# headtracking.net
KiCad netlist of a schematic drawn in Altium Designer
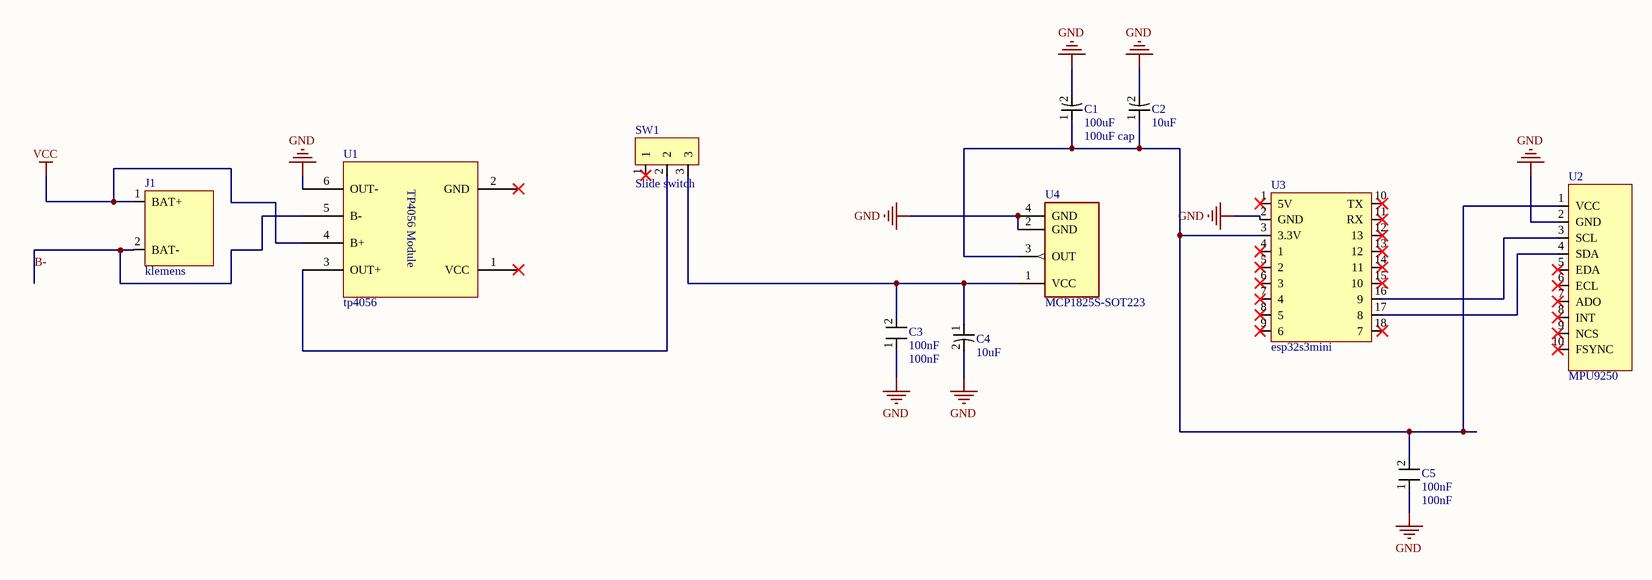
[diagram p0: headtracking.SchDoc]

(export (version "E")
  (design (tool "Eeschema 10.0.6"))
  (components
    (comp (ref "C1")
      (value "100uF cap")
      (footprint "electrytic cap")
      (fields (field (name "ALTIUM_VALUE") "100uF"))
      (libsource (lib "Integrated_Library1") (part "100uF cap"))
    )
    (comp (ref "C2")
      (value "10uF")
      (footprint "electrytic cap")
      (libsource (lib "Integrated_Library1") (part "10uF cap"))
    )
    (comp (ref "C3")
      (value "100nF")
      (footprint "ceramic cap")
      (fields (field (name "ALTIUM_VALUE") "100nF"))
      (libsource (lib "Integrated_Library1") (part "100nf cap"))
    )
    (comp (ref "C4")
      (value "10uF")
      (footprint "electrytic cap")
      (libsource (lib "Integrated_Library1") (part "10uF cap"))
    )
    (comp (ref "C5")
      (value "100nF")
      (footprint "ceramic cap")
      (fields (field (name "ALTIUM_VALUE") "100nF"))
      (libsource (lib "Integrated_Library1") (part "100nf cap"))
    )
    (comp (ref "J1")
      (value "klemens")
      (footprint "PCB_Klemens")
      (libsource (lib "Integrated_Library1") (part "klemens"))
    )
    (comp (ref "SW1")
      (value "Slide switch")
      (footprint "slide switch")
      (libsource (lib "Integrated_Library1") (part "Slide switch"))
    )
    (comp (ref "U1")
      (value "tp4056")
      (footprint "tp4056")
      (libsource (lib "Integrated_Library1") (part "tp4056"))
    )
    (comp (ref "U2")
      (value "MPU9250")
      (footprint "mpu9250")
      (libsource (lib "Integrated_Library1") (part "MPU9250"))
    )
    (comp (ref "U3")
      (value "esp32s3mini")
      (footprint "ESP32_S3_MINI")
      (libsource (lib "Integrated_Library1") (part "esp32s3mini"))
    )
    (comp (ref "U4")
      (value "MCP1825S-SOT223")
      (footprint "SOT-223 - regulator")
      (fields (field (name "MF") "Smartec") (field (name "MP") "SMT172-SOT223"))
      (libsource (lib "Integrated_Library1") (part "MCP1825S-SOT223"))
    )
  )
  (nets
    (net (code "1") (name "/B-") (class "Default")
      (node (ref "J1") (pin "2") (pinfunction "BAT-_2") (pintype "passive"))
      (node (ref "U1") (pin "5") (pinfunction "B-_5") (pintype "passive"))
    )
    (net (code "2") (name "GND") (class "Default")
      (node (ref "C1") (pin "2") (pintype "passive"))
      (node (ref "C2") (pin "2") (pintype "passive"))
      (node (ref "C3") (pin "1") (pintype "passive"))
      (node (ref "C4") (pin "2") (pintype "passive"))
      (node (ref "C5") (pin "1") (pintype "passive"))
      (node (ref "U1") (pin "6") (pinfunction "OUT-_6") (pintype "passive"))
      (node (ref "U2") (pin "2") (pinfunction "GND_2") (pintype "passive"))
      (node (ref "U3") (pin "2") (pinfunction "GND_2") (pintype "passive"))
      (node (ref "U4") (pin "2") (pinfunction "GND_2") (pintype "power_in"))
      (node (ref "U4") (pin "4") (pinfunction "GND_4") (pintype "power_in"))
    )
    (net (code "3") (name "Net-(U1-OUT+)") (class "Default")
      (node (ref "SW1") (pin "2") (pinfunction "2_2") (pintype "passive"))
      (node (ref "U1") (pin "3") (pinfunction "OUT+_3") (pintype "passive"))
    )
    (net (code "4") (name "Net-(U2-SCL)") (class "Default")
      (node (ref "U2") (pin "3") (pinfunction "SCL_3") (pintype "passive"))
      (node (ref "U3") (pin "16") (pinfunction "9_16") (pintype "passive"))
    )
    (net (code "5") (name "Net-(U2-SDA)") (class "Default")
      (node (ref "U2") (pin "4") (pinfunction "SDA_4") (pintype "passive"))
      (node (ref "U3") (pin "17") (pinfunction "8_17") (pintype "passive"))
    )
    (net (code "6") (name "Net-(U2-VCC)") (class "Default")
      (node (ref "C1") (pin "1") (pintype "passive"))
      (node (ref "C2") (pin "1") (pintype "passive"))
      (node (ref "C5") (pin "2") (pintype "passive"))
      (node (ref "U2") (pin "1") (pinfunction "VCC_1") (pintype "passive"))
      (node (ref "U3") (pin "3") (pinfunction "3.3V_3") (pintype "passive"))
      (node (ref "U4") (pin "3") (pinfunction "OUT_3") (pintype "output"))
    )
    (net (code "7") (name "Net-(U4-VCC)") (class "Default")
      (node (ref "C3") (pin "2") (pintype "passive"))
      (node (ref "C4") (pin "1") (pintype "passive"))
      (node (ref "SW1") (pin "3") (pinfunction "3_3") (pintype "passive"))
      (node (ref "U4") (pin "1") (pinfunction "VCC_1") (pintype "power_in"))
    )
    (net (code "8") (name "VCC") (class "Default")
      (node (ref "J1") (pin "1") (pinfunction "BAT+_1") (pintype "passive"))
      (node (ref "U1") (pin "4") (pinfunction "B+_4") (pintype "passive"))
    )
    (net (code "9") (name "unconnected-(SW1-Pad1)") (class "Default")
      (node (ref "SW1") (pin "1") (pinfunction "1_1") (pintype "passive+no_connect"))
    )
    (net (code "10") (name "unconnected-(U1-GND-Pad2)") (class "Default")
      (node (ref "U1") (pin "2") (pinfunction "GND_2") (pintype "passive+no_connect"))
    )
    (net (code "11") (name "unconnected-(U1-VCC-Pad1)") (class "Default")
      (node (ref "U1") (pin "1") (pinfunction "VCC_1") (pintype "passive+no_connect"))
    )
    (net (code "12") (name "unconnected-(U2-ADO-Pad7)") (class "Default")
      (node (ref "U2") (pin "7") (pinfunction "ADO_7") (pintype "passive+no_connect"))
    )
    (net (code "13") (name "unconnected-(U2-ECL-Pad6)") (class "Default")
      (node (ref "U2") (pin "6") (pinfunction "ECL_6") (pintype "passive+no_connect"))
    )
    (net (code "14") (name "unconnected-(U2-EDA-Pad5)") (class "Default")
      (node (ref "U2") (pin "5") (pinfunction "EDA_5") (pintype "passive+no_connect"))
    )
    (net (code "15") (name "unconnected-(U2-FSYNC-Pad10)") (class "Default")
      (node (ref "U2") (pin "10") (pinfunction "FSYNC_10") (pintype "passive+no_connect"))
    )
    (net (code "16") (name "unconnected-(U2-INT-Pad8)") (class "Default")
      (node (ref "U2") (pin "8") (pinfunction "INT_8") (pintype "passive+no_connect"))
    )
    (net (code "17") (name "unconnected-(U2-NCS-Pad9)") (class "Default")
      (node (ref "U2") (pin "9") (pinfunction "NCS_9") (pintype "passive+no_connect"))
    )
    (net (code "18") (name "unconnected-(U3-1-Pad4)") (class "Default")
      (node (ref "U3") (pin "4") (pinfunction "1_4") (pintype "passive+no_connect"))
    )
    (net (code "19") (name "unconnected-(U3-2-Pad5)") (class "Default")
      (node (ref "U3") (pin "5") (pinfunction "2_5") (pintype "passive+no_connect"))
    )
    (net (code "20") (name "unconnected-(U3-3-Pad6)") (class "Default")
      (node (ref "U3") (pin "6") (pinfunction "3_6") (pintype "passive+no_connect"))
    )
    (net (code "21") (name "unconnected-(U3-4-Pad7)") (class "Default")
      (node (ref "U3") (pin "7") (pinfunction "4_7") (pintype "passive+no_connect"))
    )
    (net (code "22") (name "unconnected-(U3-5-Pad8)") (class "Default")
      (node (ref "U3") (pin "8") (pinfunction "5_8") (pintype "passive+no_connect"))
    )
    (net (code "23") (name "unconnected-(U3-5V-Pad1)") (class "Default")
      (node (ref "U3") (pin "1") (pinfunction "5V_1") (pintype "passive+no_connect"))
    )
    (net (code "24") (name "unconnected-(U3-6-Pad9)") (class "Default")
      (node (ref "U3") (pin "9") (pinfunction "6_9") (pintype "passive+no_connect"))
    )
    (net (code "25") (name "unconnected-(U3-7-Pad18)") (class "Default")
      (node (ref "U3") (pin "18") (pinfunction "7_18") (pintype "passive+no_connect"))
    )
    (net (code "26") (name "unconnected-(U3-10-Pad15)") (class "Default")
      (node (ref "U3") (pin "15") (pinfunction "10_15") (pintype "passive+no_connect"))
    )
    (net (code "27") (name "unconnected-(U3-11-Pad14)") (class "Default")
      (node (ref "U3") (pin "14") (pinfunction "11_14") (pintype "passive+no_connect"))
    )
    (net (code "28") (name "unconnected-(U3-12-Pad13)") (class "Default")
      (node (ref "U3") (pin "13") (pinfunction "12_13") (pintype "passive+no_connect"))
    )
    (net (code "29") (name "unconnected-(U3-13-Pad12)") (class "Default")
      (node (ref "U3") (pin "12") (pinfunction "13_12") (pintype "passive+no_connect"))
    )
    (net (code "30") (name "unconnected-(U3-RX-Pad11)") (class "Default")
      (node (ref "U3") (pin "11") (pinfunction "RX_11") (pintype "passive+no_connect"))
    )
    (net (code "31") (name "unconnected-(U3-TX-Pad10)") (class "Default")
      (node (ref "U3") (pin "10") (pinfunction "TX_10") (pintype "passive+no_connect"))
    )
  )
)
